# PSPS_AVNC_MITCH_2021-02-25.net
KiCad netlist of a schematic drawn in EAGLE
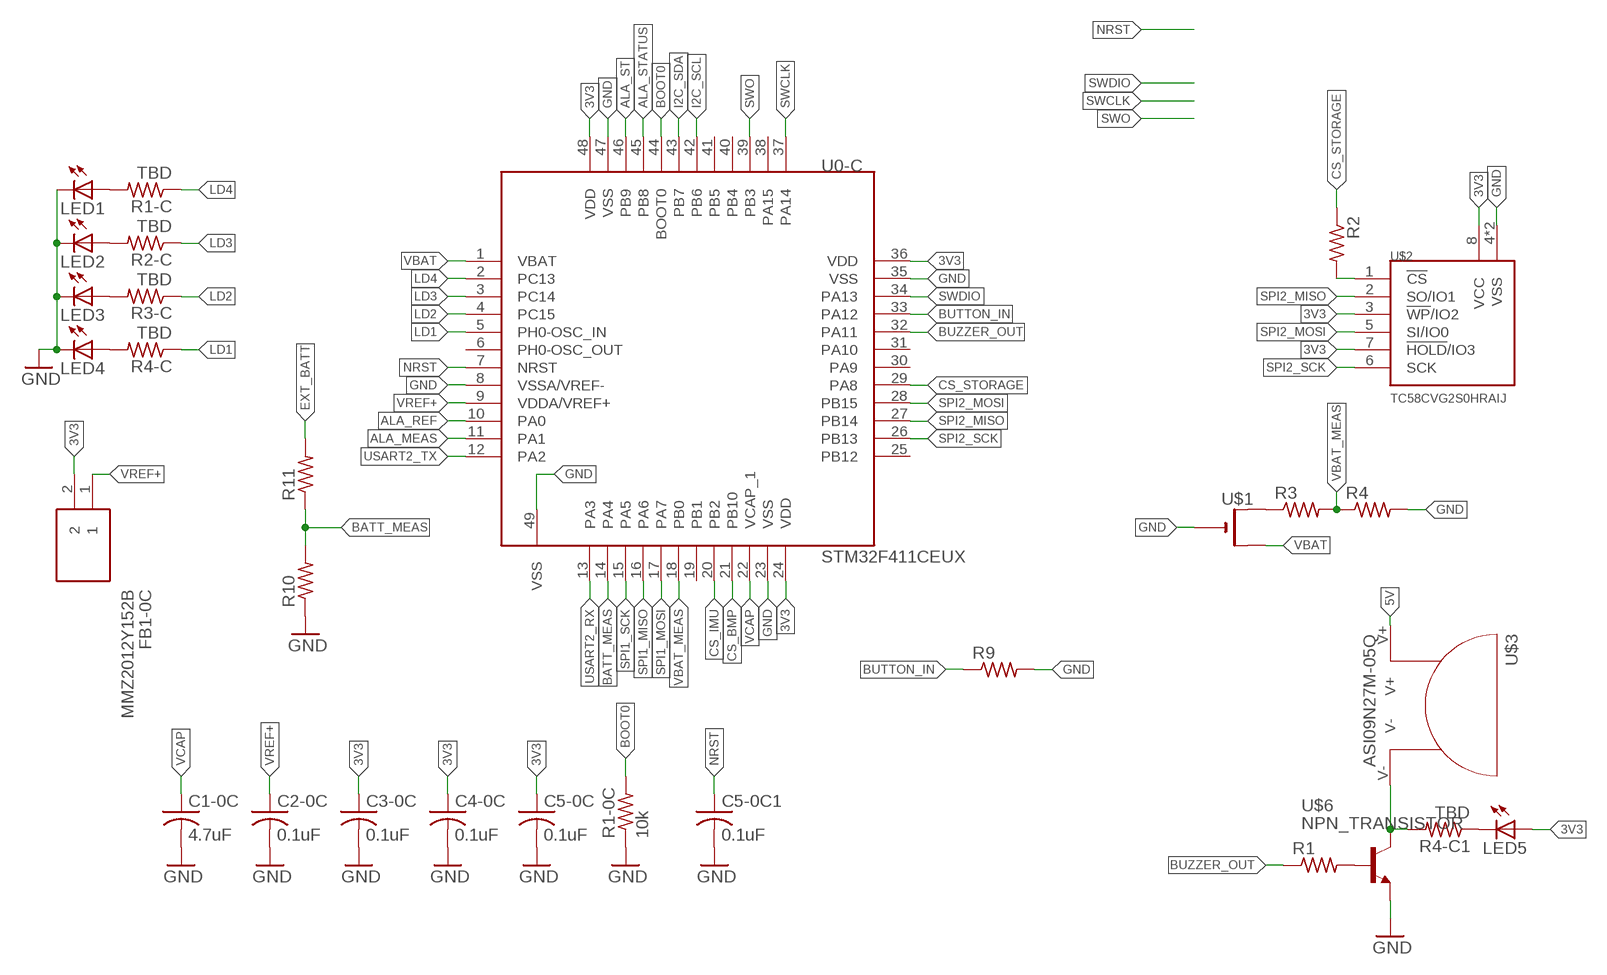
[diagram p0: schematic, sheet 1]
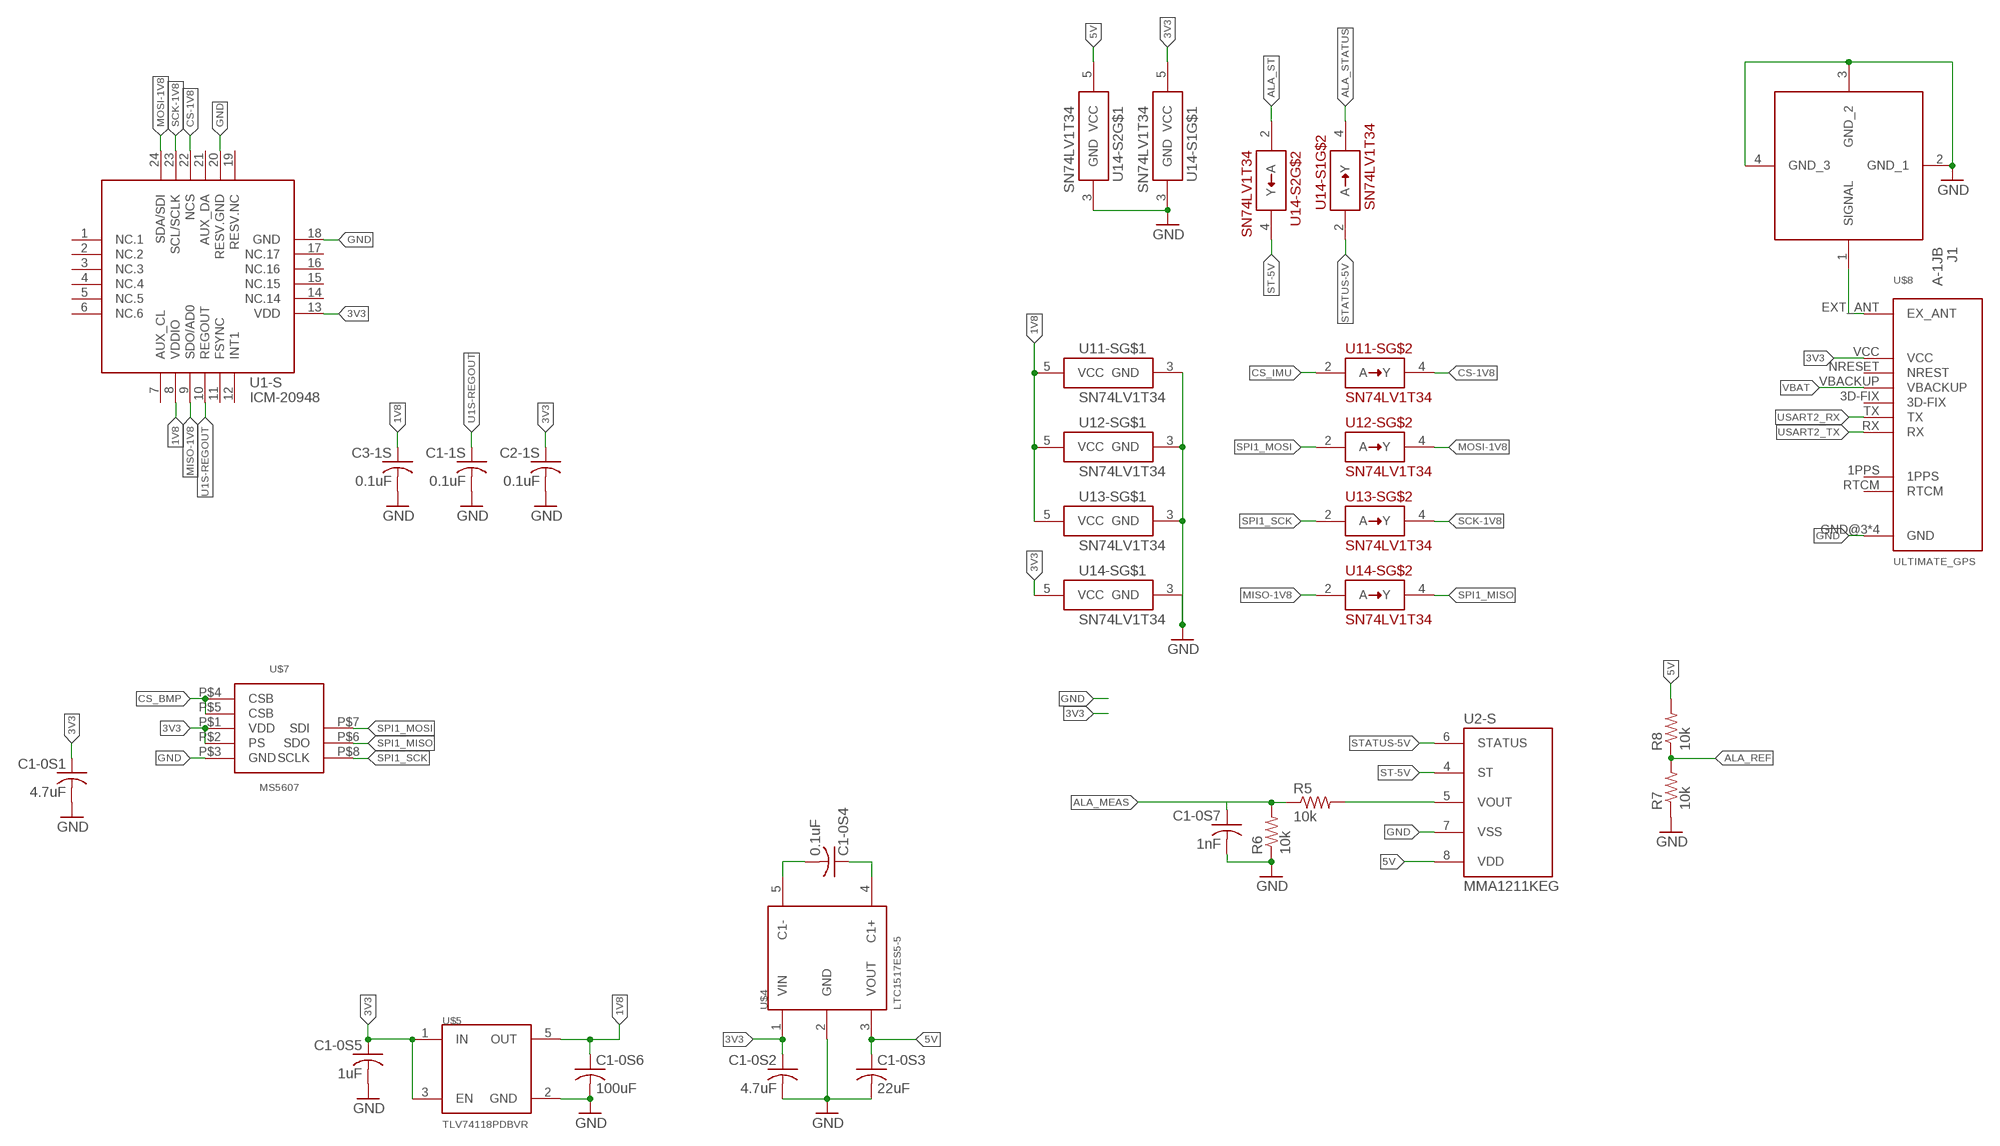
[diagram p1: schematic, sheet 2]

(export (version "E")
  (design (tool "Eeschema 10.0.6"))
  (components
    (comp (ref "C1-0S1")
      (value "4.7uF")
      (footprint "eagle-import:C0805")
      (libsource (lib "eagle-import") (part "C-USC0805"))
    )
    (comp (ref "C1-0S2")
      (value "4.7uF")
      (footprint "eagle-import:C0805")
      (libsource (lib "eagle-import") (part "C-USC0805"))
    )
    (comp (ref "C1-0S3")
      (value "22uF")
      (footprint "eagle-import:C0805")
      (libsource (lib "eagle-import") (part "C-USC0805"))
    )
    (comp (ref "C1-0S4")
      (value "0.1uF")
      (footprint "eagle-import:C0805")
      (libsource (lib "eagle-import") (part "C-USC0805"))
    )
    (comp (ref "C1-0S5")
      (value "1uF")
      (footprint "eagle-import:C0805")
      (libsource (lib "eagle-import") (part "C-USC0805"))
    )
    (comp (ref "C1-0S6")
      (value "100uF")
      (footprint "eagle-import:C0805")
      (libsource (lib "eagle-import") (part "C-USC0805"))
    )
    (comp (ref "C1-0S7")
      (value "1nF")
      (footprint "eagle-import:C0805")
      (libsource (lib "eagle-import") (part "C-USC0805"))
    )
    (comp (ref "C1-1S")
      (value "0.1uF")
      (footprint "eagle-import:C0805")
      (libsource (lib "eagle-import") (part "C-USC0805"))
    )
    (comp (ref "C2-1S")
      (value "0.1uF")
      (footprint "eagle-import:C0805")
      (libsource (lib "eagle-import") (part "C-USC0805"))
    )
    (comp (ref "C3-1S")
      (value "0.1uF")
      (footprint "eagle-import:C0805")
      (libsource (lib "eagle-import") (part "C-USC0805"))
    )
    (comp (ref "J1")
      (value "A-1JB")
      (footprint "eagle-import:A1JB")
      (fields (field (name "MOUSER_PART_NUMBER") "523-A-1JB"))
      (libsource (lib "eagle-import") (part "A-1JB"))
    )
    (comp (ref "R5")
      (value "10k")
      (footprint "eagle-import:R0805")
      (libsource (lib "eagle-import") (part "R-US_R0805"))
    )
    (comp (ref "R6")
      (value "10k")
      (footprint "eagle-import:R0805")
      (libsource (lib "eagle-import") (part "R-US_R0805"))
    )
    (comp (ref "R7")
      (value "10k")
      (footprint "eagle-import:R0805")
      (libsource (lib "eagle-import") (part "R-US_R0805"))
    )
    (comp (ref "R8")
      (value "10k")
      (footprint "eagle-import:R0805")
      (libsource (lib "eagle-import") (part "R-US_R0805"))
    )
    (comp (ref "U$4")
      (value "LTC1517ES5-5")
      (footprint "eagle-import:SOT95P280X145-5N")
      (libsource (lib "eagle-import") (part "LTC1517ES5-5"))
    )
    (comp (ref "U$5")
      (value "TLV74118PDBVR")
      (footprint "eagle-import:SOT95P280X145-5N")
      (libsource (lib "eagle-import") (part "TLV74118PDBVR"))
    )
    (comp (ref "U$7")
      (value "MS5607")
      (footprint "eagle-import:MS5607")
      (libsource (lib "eagle-import") (part "MS5607"))
    )
    (comp (ref "U$8")
      (value "ULTIMATE_GPS")
      (footprint "eagle-import:FGPMMOPA6H")
      (libsource (lib "eagle-import") (part "ULTIMATE_GPS"))
    )
    (comp (ref "U1-S")
      (value "ICM-20948")
      (footprint "eagle-import:QFN40P300X300X105-25T159X175")
      (libsource (lib "eagle-import") (part "ICM-20948"))
    )
    (comp (ref "U2-S")
      (value "MMA1211KEG")
      (footprint "eagle-import:SOIC127P1041X355-16N")
      (libsource (lib "eagle-import") (part "MMA1211KEG"))
    )
    (comp (ref "U11-S")
      (value "SN74LV1T34")
      (footprint "eagle-import:SOT65P210X110-5")
      (libsource (lib "eagle-import") (part "SN74LV1T34"))
    )
    (comp (ref "U12-S")
      (value "SN74LV1T34")
      (footprint "eagle-import:SOT65P210X110-5")
      (libsource (lib "eagle-import") (part "SN74LV1T34"))
    )
    (comp (ref "U13-S")
      (value "SN74LV1T34")
      (footprint "eagle-import:SOT65P210X110-5")
      (libsource (lib "eagle-import") (part "SN74LV1T34"))
    )
    (comp (ref "U14-S")
      (value "SN74LV1T34")
      (footprint "eagle-import:SOT65P210X110-5")
      (libsource (lib "eagle-import") (part "SN74LV1T34"))
    )
    (comp (ref "U14-S1")
      (value "SN74LV1T34")
      (footprint "eagle-import:SOT65P210X110-5")
      (libsource (lib "eagle-import") (part "SN74LV1T34"))
    )
    (comp (ref "U14-S2")
      (value "SN74LV1T34")
      (footprint "eagle-import:SOT65P210X110-5")
      (libsource (lib "eagle-import") (part "SN74LV1T34"))
    )
    (comp (ref "C1-0C")
      (value "4.7uF")
      (footprint "eagle-import:C0805")
      (libsource (lib "eagle-import") (part "C-USC0805"))
    )
    (comp (ref "C2-0C")
      (value "0.1uF")
      (footprint "eagle-import:C0805")
      (libsource (lib "eagle-import") (part "C-USC0805"))
    )
    (comp (ref "C3-0C")
      (value "0.1uF")
      (footprint "eagle-import:C0805")
      (libsource (lib "eagle-import") (part "C-USC0805"))
    )
    (comp (ref "C4-0C")
      (value "0.1uF")
      (footprint "eagle-import:C0805")
      (libsource (lib "eagle-import") (part "C-USC0805"))
    )
    (comp (ref "C5-0C")
      (value "0.1uF")
      (footprint "eagle-import:C0805")
      (libsource (lib "eagle-import") (part "C-USC0805"))
    )
    (comp (ref "C5-0C1")
      (value "0.1uF")
      (footprint "eagle-import:C0805")
      (libsource (lib "eagle-import") (part "C-USC0805"))
    )
    (comp (ref "FB1-0C")
      (value "MMZ2012Y152B")
      (footprint "eagle-import:BEADC2012X105N")
      (fields (field (name "MOUSER_PART_NUMBER") "810-MMZ2012Y152B"))
      (libsource (lib "eagle-import") (part "MMZ2012Y152B"))
    )
    (comp (ref "LED1")
      (value "LEDCHIPLED_0805")
      (footprint "eagle-import:CHIPLED_0805")
      (libsource (lib "eagle-import") (part "LEDCHIPLED_0805"))
    )
    (comp (ref "LED2")
      (value "LEDCHIPLED_0805")
      (footprint "eagle-import:CHIPLED_0805")
      (libsource (lib "eagle-import") (part "LEDCHIPLED_0805"))
    )
    (comp (ref "LED3")
      (value "LEDCHIPLED_0805")
      (footprint "eagle-import:CHIPLED_0805")
      (libsource (lib "eagle-import") (part "LEDCHIPLED_0805"))
    )
    (comp (ref "LED4")
      (value "LEDCHIPLED_0805")
      (footprint "eagle-import:CHIPLED_0805")
      (libsource (lib "eagle-import") (part "LEDCHIPLED_0805"))
    )
    (comp (ref "LED5")
      (value "LEDCHIPLED_0805")
      (footprint "eagle-import:CHIPLED_0805")
      (libsource (lib "eagle-import") (part "LEDCHIPLED_0805"))
    )
    (comp (ref "R1")
      (value "R-US_R0805")
      (footprint "eagle-import:R0805")
      (libsource (lib "eagle-import") (part "R-US_R0805"))
    )
    (comp (ref "R1-0C")
      (value "10k")
      (footprint "eagle-import:R0805")
      (libsource (lib "eagle-import") (part "R-US_R0805"))
    )
    (comp (ref "R1-C")
      (value "TBD")
      (footprint "eagle-import:R0805")
      (libsource (lib "eagle-import") (part "R-US_R0805"))
    )
    (comp (ref "R2")
      (value "R-US_R0805")
      (footprint "eagle-import:R0805")
      (libsource (lib "eagle-import") (part "R-US_R0805"))
    )
    (comp (ref "R2-C")
      (value "TBD")
      (footprint "eagle-import:R0805")
      (libsource (lib "eagle-import") (part "R-US_R0805"))
    )
    (comp (ref "R3")
      (value "R-US_R0805")
      (footprint "eagle-import:R0805")
      (libsource (lib "eagle-import") (part "R-US_R0805"))
    )
    (comp (ref "R3-C")
      (value "TBD")
      (footprint "eagle-import:R0805")
      (libsource (lib "eagle-import") (part "R-US_R0805"))
    )
    (comp (ref "R4")
      (value "R-US_R0805")
      (footprint "eagle-import:R0805")
      (libsource (lib "eagle-import") (part "R-US_R0805"))
    )
    (comp (ref "R4-C")
      (value "TBD")
      (footprint "eagle-import:R0805")
      (libsource (lib "eagle-import") (part "R-US_R0805"))
    )
    (comp (ref "R4-C1")
      (value "TBD")
      (footprint "eagle-import:R0805")
      (libsource (lib "eagle-import") (part "R-US_R0805"))
    )
    (comp (ref "R9")
      (value "R-US_R0805")
      (footprint "eagle-import:R0805")
      (libsource (lib "eagle-import") (part "R-US_R0805"))
    )
    (comp (ref "R10")
      (value "R-US_R0805")
      (footprint "eagle-import:R0805")
      (libsource (lib "eagle-import") (part "R-US_R0805"))
    )
    (comp (ref "R11")
      (value "R-US_R0805")
      (footprint "eagle-import:R0805")
      (libsource (lib "eagle-import") (part "R-US_R0805"))
    )
    (comp (ref "U$1")
      (value "CR1220SMT")
      (footprint "eagle-import:CR1220-SMD")
      (libsource (lib "eagle-import") (part "CR1220SMT"))
    )
    (comp (ref "U$2")
      (value "TC58CVG2S0HRAIJ")
      (footprint "eagle-import:SON127P800X600X80-9T350X440N")
      (libsource (lib "eagle-import") (part "TC58CVG2S0HRAIJ"))
    )
    (comp (ref "U$3")
      (value "ASI09N27M-05Q")
      (footprint "eagle-import:ASI09N27M-05Q")
      (libsource (lib "eagle-import") (part "ASI09N27M-05Q"))
    )
    (comp (ref "U$6")
      (value "NPN_TRANSISTOR")
      (footprint "eagle-import:SOT23")
      (libsource (lib "eagle-import") (part "NPN_TRANSISTOR"))
    )
    (comp (ref "U0-C")
      (value "STM32F411CEUX")
      (footprint "eagle-import:QFN50P700X700X50-49T560N")
      (libsource (lib "eagle-import") (part "STM32F411CEUX"))
    )
  )
  (nets
    (net (code "1") (name "1V8") (class "Default")
      (node (ref "C1-0S6") (pin "1") (pinfunction "1_1") (pintype "passive"))
      (node (ref "C3-1S") (pin "1") (pinfunction "1_1") (pintype "passive"))
      (node (ref "U$5") (pin "5") (pinfunction "OUT_5") (pintype "bidirectional"))
      (node (ref "U1-S") (pin "8") (pinfunction "VDDIO_8") (pintype "bidirectional"))
      (node (ref "U11-S") (pin "5") (pinfunction "VCC_5") (pintype "bidirectional"))
      (node (ref "U12-S") (pin "5") (pinfunction "VCC_5") (pintype "bidirectional"))
      (node (ref "U13-S") (pin "5") (pinfunction "VCC_5") (pintype "bidirectional"))
    )
    (net (code "2") (name "3V3") (class "Default")
      (node (ref "C1-0S1") (pin "1") (pinfunction "1_1") (pintype "passive"))
      (node (ref "C1-0S2") (pin "1") (pinfunction "1_1") (pintype "passive"))
      (node (ref "C1-0S5") (pin "1") (pinfunction "1_1") (pintype "passive"))
      (node (ref "C2-1S") (pin "1") (pinfunction "1_1") (pintype "passive"))
      (node (ref "C3-0C") (pin "1") (pinfunction "1_1") (pintype "passive"))
      (node (ref "C4-0C") (pin "1") (pinfunction "1_1") (pintype "passive"))
      (node (ref "C5-0C") (pin "1") (pinfunction "1_1") (pintype "passive"))
      (node (ref "FB1-0C") (pin "2") (pinfunction "2_2") (pintype "bidirectional"))
      (node (ref "LED5") (pin "A") (pinfunction "A_A") (pintype "passive"))
      (node (ref "U$2") (pin "3") (pinfunction "~{WP}/IO2_3") (pintype "bidirectional"))
      (node (ref "U$2") (pin "7") (pinfunction "~{HOLD}/IO3_7") (pintype "bidirectional"))
      (node (ref "U$2") (pin "8") (pinfunction "VCC_8") (pintype "bidirectional"))
      (node (ref "U$4") (pin "1") (pinfunction "VIN_1") (pintype "bidirectional"))
      (node (ref "U$5") (pin "1") (pinfunction "IN_1") (pintype "bidirectional"))
      (node (ref "U$5") (pin "3") (pinfunction "EN_3") (pintype "bidirectional"))
      (node (ref "U$7") (pin "P$1") (pinfunction "VDD_P$1") (pintype "bidirectional"))
      (node (ref "U$7") (pin "P$2") (pinfunction "PS_P$2") (pintype "bidirectional"))
      (node (ref "U$8") (pin "VCC") (pinfunction "VCC_VCC") (pintype "bidirectional"))
      (node (ref "U0-C") (pin "24") (pinfunction "VDD_24") (pintype "bidirectional"))
      (node (ref "U0-C") (pin "36") (pinfunction "VDD_36") (pintype "bidirectional"))
      (node (ref "U0-C") (pin "48") (pinfunction "VDD_48") (pintype "bidirectional"))
      (node (ref "U1-S") (pin "13") (pinfunction "VDD_13") (pintype "bidirectional"))
      (node (ref "U14-S") (pin "5") (pinfunction "VCC_5") (pintype "bidirectional"))
      (node (ref "U14-S1") (pin "5") (pinfunction "VCC_5") (pintype "bidirectional"))
    )
    (net (code "3") (name "5V") (class "Default")
      (node (ref "C1-0S3") (pin "1") (pinfunction "1_1") (pintype "passive"))
      (node (ref "R8") (pin "2") (pinfunction "2_2") (pintype "passive"))
      (node (ref "U$3") (pin "V+") (pinfunction "V+_V+") (pintype "bidirectional"))
      (node (ref "U$4") (pin "3") (pinfunction "VOUT_3") (pintype "bidirectional"))
      (node (ref "U14-S2") (pin "5") (pinfunction "VCC_5") (pintype "bidirectional"))
      (node (ref "U2-S") (pin "8") (pinfunction "VDD_8") (pintype "bidirectional"))
    )
    (net (code "4") (name "ALA_MEAS") (class "Default")
      (node (ref "C1-0S7") (pin "1") (pinfunction "1_1") (pintype "passive"))
      (node (ref "R5") (pin "1") (pinfunction "1_1") (pintype "passive"))
      (node (ref "R6") (pin "2") (pinfunction "2_2") (pintype "passive"))
      (node (ref "U0-C") (pin "11") (pinfunction "PA1_11") (pintype "bidirectional"))
    )
    (net (code "5") (name "ALA_REF") (class "Default")
      (node (ref "R7") (pin "2") (pinfunction "2_2") (pintype "passive"))
      (node (ref "R8") (pin "1") (pinfunction "1_1") (pintype "passive"))
      (node (ref "U0-C") (pin "10") (pinfunction "PA0_10") (pintype "bidirectional"))
    )
    (net (code "6") (name "ALA_ST") (class "Default")
      (node (ref "U0-C") (pin "46") (pinfunction "PB9_46") (pintype "bidirectional"))
      (node (ref "U14-S2") (pin "2") (pinfunction "A_2") (pintype "bidirectional"))
    )
    (net (code "7") (name "ALA_STATUS") (class "Default")
      (node (ref "U0-C") (pin "45") (pinfunction "PB8_45") (pintype "bidirectional"))
      (node (ref "U14-S1") (pin "4") (pinfunction "Y_4") (pintype "bidirectional"))
    )
    (net (code "8") (name "BATT_MEAS") (class "Default")
      (node (ref "R10") (pin "2") (pinfunction "2_2") (pintype "passive"))
      (node (ref "R11") (pin "1") (pinfunction "1_1") (pintype "passive"))
      (node (ref "U0-C") (pin "14") (pinfunction "PA4_14") (pintype "bidirectional"))
    )
    (net (code "9") (name "BOOT0") (class "Default")
      (node (ref "R1-0C") (pin "2") (pinfunction "2_2") (pintype "passive"))
      (node (ref "U0-C") (pin "44") (pinfunction "BOOT0_44") (pintype "bidirectional"))
    )
    (net (code "10") (name "BUTTON_IN") (class "Default")
      (node (ref "R9") (pin "1") (pinfunction "1_1") (pintype "passive"))
      (node (ref "U0-C") (pin "33") (pinfunction "PA12_33") (pintype "bidirectional"))
    )
    (net (code "11") (name "BUZZER_OUT") (class "Default")
      (node (ref "R1") (pin "1") (pinfunction "1_1") (pintype "passive"))
      (node (ref "U0-C") (pin "32") (pinfunction "PA11_32") (pintype "bidirectional"))
    )
    (net (code "12") (name "CS-1V8") (class "Default")
      (node (ref "U1-S") (pin "22") (pinfunction "NCS_22") (pintype "bidirectional"))
      (node (ref "U11-S") (pin "4") (pinfunction "Y_4") (pintype "bidirectional"))
    )
    (net (code "13") (name "CS_BMP") (class "Default")
      (node (ref "U$7") (pin "P$4") (pinfunction "CSB_P$4") (pintype "bidirectional"))
      (node (ref "U$7") (pin "P$5") (pinfunction "CSB_P$5") (pintype "bidirectional"))
      (node (ref "U0-C") (pin "21") (pinfunction "PB10_21") (pintype "bidirectional"))
    )
    (net (code "14") (name "CS_IMU") (class "Default")
      (node (ref "U0-C") (pin "20") (pinfunction "PB2_20") (pintype "bidirectional"))
      (node (ref "U11-S") (pin "2") (pinfunction "A_2") (pintype "bidirectional"))
    )
    (net (code "15") (name "CS_STORAGE") (class "Default")
      (node (ref "R2") (pin "1") (pinfunction "1_1") (pintype "passive"))
      (node (ref "U0-C") (pin "29") (pinfunction "PA8_29") (pintype "bidirectional"))
    )
    (net (code "16") (name "EXT_BATT") (class "Default")
      (node (ref "R11") (pin "2") (pinfunction "2_2") (pintype "passive"))
    )
    (net (code "17") (name "GND") (class "Default")
      (node (ref "C1-0C") (pin "2") (pinfunction "2_2") (pintype "passive"))
      (node (ref "C1-0S1") (pin "2") (pinfunction "2_2") (pintype "passive"))
      (node (ref "C1-0S2") (pin "2") (pinfunction "2_2") (pintype "passive"))
      (node (ref "C1-0S3") (pin "2") (pinfunction "2_2") (pintype "passive"))
      (node (ref "C1-0S5") (pin "2") (pinfunction "2_2") (pintype "passive"))
      (node (ref "C1-0S6") (pin "2") (pinfunction "2_2") (pintype "passive"))
      (node (ref "C1-0S7") (pin "2") (pinfunction "2_2") (pintype "passive"))
      (node (ref "C1-1S") (pin "2") (pinfunction "2_2") (pintype "passive"))
      (node (ref "C2-0C") (pin "2") (pinfunction "2_2") (pintype "passive"))
      (node (ref "C2-1S") (pin "2") (pinfunction "2_2") (pintype "passive"))
      (node (ref "C3-0C") (pin "2") (pinfunction "2_2") (pintype "passive"))
      (node (ref "C3-1S") (pin "2") (pinfunction "2_2") (pintype "passive"))
      (node (ref "C4-0C") (pin "2") (pinfunction "2_2") (pintype "passive"))
      (node (ref "C5-0C") (pin "2") (pinfunction "2_2") (pintype "passive"))
      (node (ref "C5-0C1") (pin "2") (pinfunction "2_2") (pintype "passive"))
      (node (ref "J1") (pin "2") (pinfunction "GND_1_2") (pintype "bidirectional"))
      (node (ref "J1") (pin "3") (pinfunction "GND_2_3") (pintype "bidirectional"))
      (node (ref "J1") (pin "4") (pinfunction "GND_3_4") (pintype "bidirectional"))
      (node (ref "LED1") (pin "C") (pinfunction "C_C") (pintype "passive"))
      (node (ref "LED2") (pin "C") (pinfunction "C_C") (pintype "passive"))
      (node (ref "LED3") (pin "C") (pinfunction "C_C") (pintype "passive"))
      (node (ref "LED4") (pin "C") (pinfunction "C_C") (pintype "passive"))
      (node (ref "R1-0C") (pin "1") (pinfunction "1_1") (pintype "passive"))
      (node (ref "R10") (pin "1") (pinfunction "1_1") (pintype "passive"))
      (node (ref "R4") (pin "2") (pinfunction "2_2") (pintype "passive"))
      (node (ref "R6") (pin "1") (pinfunction "1_1") (pintype "passive"))
      (node (ref "R7") (pin "1") (pinfunction "1_1") (pintype "passive"))
      (node (ref "R9") (pin "2") (pinfunction "2_2") (pintype "passive"))
      (node (ref "U$1") (pin "-") (pinfunction "-_-") (pintype "passive"))
      (node (ref "U$2") (pin "4") (pinfunction "VSS_4") (pintype "bidirectional"))
      (node (ref "U$2") (pin "9") (pinfunction "VSS_9") (pintype "bidirectional"))
      (node (ref "U$4") (pin "2") (pinfunction "GND_2") (pintype "bidirectional"))
      (node (ref "U$5") (pin "2") (pinfunction "GND_2") (pintype "bidirectional"))
      (node (ref "U$6") (pin "3") (pinfunction "E_3") (pintype "passive"))
      (node (ref "U$7") (pin "P$3") (pinfunction "GND_P$3") (pintype "bidirectional"))
      (node (ref "U$8") (pin "GND@12") (pinfunction "GND_GND@12") (pintype "bidirectional"))
      (node (ref "U$8") (pin "GND@19") (pinfunction "GND_GND@19") (pintype "bidirectional"))
      (node (ref "U$8") (pin "GND@3") (pinfunction "GND_GND@3") (pintype "bidirectional"))
      (node (ref "U$8") (pin "GND@8") (pinfunction "GND_GND@8") (pintype "bidirectional"))
      (node (ref "U0-C") (pin "23") (pinfunction "VSS_23") (pintype "bidirectional"))
      (node (ref "U0-C") (pin "35") (pinfunction "VSS_35") (pintype "bidirectional"))
      (node (ref "U0-C") (pin "47") (pinfunction "VSS_47") (pintype "bidirectional"))
      (node (ref "U0-C") (pin "49") (pinfunction "VSS_49") (pintype "bidirectional"))
      (node (ref "U0-C") (pin "8") (pinfunction "VSSA/VREF-_8") (pintype "bidirectional"))
      (node (ref "U1-S") (pin "18") (pinfunction "GND_18") (pintype "bidirectional"))
      (node (ref "U1-S") (pin "20") (pinfunction "RESV.GND_20") (pintype "bidirectional"))
      (node (ref "U11-S") (pin "3") (pinfunction "GND_3") (pintype "bidirectional"))
      (node (ref "U12-S") (pin "3") (pinfunction "GND_3") (pintype "bidirectional"))
      (node (ref "U13-S") (pin "3") (pinfunction "GND_3") (pintype "bidirectional"))
      (node (ref "U14-S") (pin "3") (pinfunction "GND_3") (pintype "bidirectional"))
      (node (ref "U14-S1") (pin "3") (pinfunction "GND_3") (pintype "bidirectional"))
      (node (ref "U14-S2") (pin "3") (pinfunction "GND_3") (pintype "bidirectional"))
      (node (ref "U2-S") (pin "7") (pinfunction "VSS_7") (pintype "bidirectional"))
    )
    (net (code "18") (name "I2C_SCL") (class "Default")
      (node (ref "U0-C") (pin "42") (pinfunction "PB6_42") (pintype "bidirectional"))
    )
    (net (code "19") (name "I2C_SDA") (class "Default")
      (node (ref "U0-C") (pin "43") (pinfunction "PB7_43") (pintype "bidirectional"))
    )
    (net (code "20") (name "LD1") (class "Default")
      (node (ref "R4-C") (pin "1") (pinfunction "1_1") (pintype "passive"))
      (node (ref "U0-C") (pin "5") (pinfunction "PH0-OSC_IN_5") (pintype "bidirectional"))
    )
    (net (code "21") (name "LD2") (class "Default")
      (node (ref "R3-C") (pin "1") (pinfunction "1_1") (pintype "passive"))
      (node (ref "U0-C") (pin "4") (pinfunction "PC15_4") (pintype "bidirectional"))
    )
    (net (code "22") (name "LD3") (class "Default")
      (node (ref "R2-C") (pin "1") (pinfunction "1_1") (pintype "passive"))
      (node (ref "U0-C") (pin "3") (pinfunction "PC14_3") (pintype "bidirectional"))
    )
    (net (code "23") (name "LD4") (class "Default")
      (node (ref "R1-C") (pin "1") (pinfunction "1_1") (pintype "passive"))
      (node (ref "U0-C") (pin "2") (pinfunction "PC13_2") (pintype "bidirectional"))
    )
    (net (code "24") (name "MISO-1V8") (class "Default")
      (node (ref "U1-S") (pin "9") (pinfunction "SDO/AD0_9") (pintype "bidirectional"))
      (node (ref "U14-S") (pin "2") (pinfunction "A_2") (pintype "bidirectional"))
    )
    (net (code "25") (name "MOSI-1V8") (class "Default")
      (node (ref "U1-S") (pin "24") (pinfunction "SDA/SDI_24") (pintype "bidirectional"))
      (node (ref "U12-S") (pin "4") (pinfunction "Y_4") (pintype "bidirectional"))
    )
    (net (code "26") (name "NRST") (class "Default")
      (node (ref "C5-0C1") (pin "1") (pinfunction "1_1") (pintype "passive"))
      (node (ref "U0-C") (pin "7") (pinfunction "NRST_7") (pintype "bidirectional"))
    )
    (net (code "27") (name "Net-(J1-SIGNAL)") (class "Default")
      (node (ref "J1") (pin "1") (pinfunction "SIGNAL_1") (pintype "bidirectional"))
      (node (ref "U$8") (pin "EXT_ANT") (pinfunction "EX_ANT_EXT_ANT") (pintype "bidirectional"))
    )
    (net (code "28") (name "Net-(LED1-PadA)") (class "Default")
      (node (ref "LED1") (pin "A") (pinfunction "A_A") (pintype "passive"))
      (node (ref "R1-C") (pin "2") (pinfunction "2_2") (pintype "passive"))
    )
    (net (code "29") (name "Net-(LED2-PadA)") (class "Default")
      (node (ref "LED2") (pin "A") (pinfunction "A_A") (pintype "passive"))
      (node (ref "R2-C") (pin "2") (pinfunction "2_2") (pintype "passive"))
    )
    (net (code "30") (name "Net-(LED3-PadA)") (class "Default")
      (node (ref "LED3") (pin "A") (pinfunction "A_A") (pintype "passive"))
      (node (ref "R3-C") (pin "2") (pinfunction "2_2") (pintype "passive"))
    )
    (net (code "31") (name "Net-(LED4-PadA)") (class "Default")
      (node (ref "LED4") (pin "A") (pinfunction "A_A") (pintype "passive"))
      (node (ref "R4-C") (pin "2") (pinfunction "2_2") (pintype "passive"))
    )
    (net (code "32") (name "Net-(LED5-PadC)") (class "Default")
      (node (ref "LED5") (pin "C") (pinfunction "C_C") (pintype "passive"))
      (node (ref "R4-C1") (pin "1") (pinfunction "1_1") (pintype "passive"))
    )
    (net (code "33") (name "Net-(U$1-+)") (class "Default")
      (node (ref "R3") (pin "1") (pinfunction "1_1") (pintype "passive"))
      (node (ref "U$1") (pin "+$1") (pinfunction "+_+$1") (pintype "passive"))
    )
    (net (code "34") (name "Net-(U$2-~{CS})") (class "Default")
      (node (ref "R2") (pin "2") (pinfunction "2_2") (pintype "passive"))
      (node (ref "U$2") (pin "1") (pinfunction "~{CS}_1") (pintype "bidirectional"))
    )
    (net (code "35") (name "Net-(U$4-C1+)") (class "Default")
      (node (ref "C1-0S4") (pin "1") (pinfunction "1_1") (pintype "passive"))
      (node (ref "U$4") (pin "4") (pinfunction "C1+_4") (pintype "bidirectional"))
    )
    (net (code "36") (name "Net-(U$4-C1-)") (class "Default")
      (node (ref "C1-0S4") (pin "2") (pinfunction "2_2") (pintype "passive"))
      (node (ref "U$4") (pin "5") (pinfunction "C1-_5") (pintype "bidirectional"))
    )
    (net (code "37") (name "Net-(U$6-B)") (class "Default")
      (node (ref "R1") (pin "2") (pinfunction "2_2") (pintype "passive"))
      (node (ref "U$6") (pin "1") (pinfunction "B_1") (pintype "passive"))
    )
    (net (code "38") (name "Net-(U$6-C)") (class "Default")
      (node (ref "R4-C1") (pin "2") (pinfunction "2_2") (pintype "passive"))
      (node (ref "U$3") (pin "V-") (pinfunction "V-_V-") (pintype "bidirectional"))
      (node (ref "U$6") (pin "2") (pinfunction "C_2") (pintype "passive"))
    )
    (net (code "39") (name "Net-(U2-S-VOUT)") (class "Default")
      (node (ref "R5") (pin "2") (pinfunction "2_2") (pintype "passive"))
      (node (ref "U2-S") (pin "5") (pinfunction "VOUT_5") (pintype "bidirectional"))
    )
    (net (code "40") (name "SCK-1V8") (class "Default")
      (node (ref "U1-S") (pin "23") (pinfunction "SCL/SCLK_23") (pintype "bidirectional"))
      (node (ref "U13-S") (pin "4") (pinfunction "Y_4") (pintype "bidirectional"))
    )
    (net (code "41") (name "SPI1_MISO") (class "Default")
      (node (ref "U$7") (pin "P$6") (pinfunction "SDO_P$6") (pintype "bidirectional"))
      (node (ref "U0-C") (pin "16") (pinfunction "PA6_16") (pintype "bidirectional"))
      (node (ref "U14-S") (pin "4") (pinfunction "Y_4") (pintype "bidirectional"))
    )
    (net (code "42") (name "SPI1_MOSI") (class "Default")
      (node (ref "U$7") (pin "P$7") (pinfunction "SDI_P$7") (pintype "bidirectional"))
      (node (ref "U0-C") (pin "17") (pinfunction "PA7_17") (pintype "bidirectional"))
      (node (ref "U12-S") (pin "2") (pinfunction "A_2") (pintype "bidirectional"))
    )
    (net (code "43") (name "SPI1_SCK") (class "Default")
      (node (ref "U$7") (pin "P$8") (pinfunction "SCLK_P$8") (pintype "bidirectional"))
      (node (ref "U0-C") (pin "15") (pinfunction "PA5_15") (pintype "bidirectional"))
      (node (ref "U13-S") (pin "2") (pinfunction "A_2") (pintype "bidirectional"))
    )
    (net (code "44") (name "SPI2_MISO") (class "Default")
      (node (ref "U$2") (pin "2") (pinfunction "SO/IO1_2") (pintype "bidirectional"))
      (node (ref "U0-C") (pin "27") (pinfunction "PB14_27") (pintype "bidirectional"))
    )
    (net (code "45") (name "SPI2_MOSI") (class "Default")
      (node (ref "U$2") (pin "5") (pinfunction "SI/IO0_5") (pintype "bidirectional"))
      (node (ref "U0-C") (pin "28") (pinfunction "PB15_28") (pintype "bidirectional"))
    )
    (net (code "46") (name "SPI2_SCK") (class "Default")
      (node (ref "U$2") (pin "6") (pinfunction "SCK_6") (pintype "bidirectional"))
      (node (ref "U0-C") (pin "26") (pinfunction "PB13_26") (pintype "bidirectional"))
    )
    (net (code "47") (name "ST-5V") (class "Default")
      (node (ref "U14-S2") (pin "4") (pinfunction "Y_4") (pintype "bidirectional"))
      (node (ref "U2-S") (pin "4") (pinfunction "ST_4") (pintype "bidirectional"))
    )
    (net (code "48") (name "STATUS-5V") (class "Default")
      (node (ref "U14-S1") (pin "2") (pinfunction "A_2") (pintype "bidirectional"))
      (node (ref "U2-S") (pin "6") (pinfunction "STATUS_6") (pintype "bidirectional"))
    )
    (net (code "49") (name "SWCLK") (class "Default")
      (node (ref "U0-C") (pin "37") (pinfunction "PA14_37") (pintype "bidirectional"))
    )
    (net (code "50") (name "SWDIO") (class "Default")
      (node (ref "U0-C") (pin "34") (pinfunction "PA13_34") (pintype "bidirectional"))
    )
    (net (code "51") (name "SWO") (class "Default")
      (node (ref "U0-C") (pin "39") (pinfunction "PB3_39") (pintype "bidirectional"))
    )
    (net (code "52") (name "U1S-REGOUT") (class "Default")
      (node (ref "C1-1S") (pin "1") (pinfunction "1_1") (pintype "passive"))
      (node (ref "U1-S") (pin "10") (pinfunction "REGOUT_10") (pintype "bidirectional"))
    )
    (net (code "53") (name "USART2_RX") (class "Default")
      (node (ref "U$8") (pin "TX") (pinfunction "TX_TX") (pintype "bidirectional"))
      (node (ref "U0-C") (pin "13") (pinfunction "PA3_13") (pintype "bidirectional"))
    )
    (net (code "54") (name "USART2_TX") (class "Default")
      (node (ref "U$8") (pin "RX") (pinfunction "RX_RX") (pintype "bidirectional"))
      (node (ref "U0-C") (pin "12") (pinfunction "PA2_12") (pintype "bidirectional"))
    )
    (net (code "55") (name "VBAT") (class "Default")
      (node (ref "U$1") (pin "+$2") (pinfunction "+1_+$2") (pintype "passive"))
      (node (ref "U$8") (pin "VBACKUP") (pinfunction "VBACKUP_VBACKUP") (pintype "bidirectional"))
      (node (ref "U0-C") (pin "1") (pinfunction "VBAT_1") (pintype "bidirectional"))
    )
    (net (code "56") (name "VBAT_MEAS") (class "Default")
      (node (ref "R3") (pin "2") (pinfunction "2_2") (pintype "passive"))
      (node (ref "R4") (pin "1") (pinfunction "1_1") (pintype "passive"))
      (node (ref "U0-C") (pin "18") (pinfunction "PB0_18") (pintype "bidirectional"))
    )
    (net (code "57") (name "VCAP") (class "Default")
      (node (ref "C1-0C") (pin "1") (pinfunction "1_1") (pintype "passive"))
      (node (ref "U0-C") (pin "22") (pinfunction "VCAP_1_22") (pintype "bidirectional"))
    )
    (net (code "58") (name "VREF+") (class "Default")
      (node (ref "C2-0C") (pin "1") (pinfunction "1_1") (pintype "passive"))
      (node (ref "FB1-0C") (pin "1") (pinfunction "1_1") (pintype "bidirectional"))
      (node (ref "U0-C") (pin "9") (pinfunction "VDDA/VREF+_9") (pintype "bidirectional"))
    )
    (net (code "59") (name "unconnected-(U$8-NREST-PadNRESET)") (class "Default")
      (node (ref "U$8") (pin "NRESET") (pinfunction "NREST_NRESET") (pintype "bidirectional"))
    )
    (net (code "60") (name "unconnected-(U$8-Pad1PPS)") (class "Default")
      (node (ref "U$8") (pin "1PPS") (pinfunction "1PPS_1PPS") (pintype "bidirectional"))
    )
    (net (code "61") (name "unconnected-(U$8-Pad3D-FIX)") (class "Default")
      (node (ref "U$8") (pin "3D-FIX") (pinfunction "3D-FIX_3D-FIX") (pintype "bidirectional"))
    )
    (net (code "62") (name "unconnected-(U$8-PadRTCM)") (class "Default")
      (node (ref "U$8") (pin "RTCM") (pinfunction "RTCM_RTCM") (pintype "bidirectional"))
    )
    (net (code "63") (name "unconnected-(U0-C-PA9-Pad30)") (class "Default")
      (node (ref "U0-C") (pin "30") (pinfunction "PA9_30") (pintype "bidirectional"))
    )
    (net (code "64") (name "unconnected-(U0-C-PA10-Pad31)") (class "Default")
      (node (ref "U0-C") (pin "31") (pinfunction "PA10_31") (pintype "bidirectional"))
    )
    (net (code "65") (name "unconnected-(U0-C-PA15-Pad38)") (class "Default")
      (node (ref "U0-C") (pin "38") (pinfunction "PA15_38") (pintype "bidirectional"))
    )
    (net (code "66") (name "unconnected-(U0-C-PB1-Pad19)") (class "Default")
      (node (ref "U0-C") (pin "19") (pinfunction "PB1_19") (pintype "bidirectional"))
    )
    (net (code "67") (name "unconnected-(U0-C-PB4-Pad40)") (class "Default")
      (node (ref "U0-C") (pin "40") (pinfunction "PB4_40") (pintype "bidirectional"))
    )
    (net (code "68") (name "unconnected-(U0-C-PB5-Pad41)") (class "Default")
      (node (ref "U0-C") (pin "41") (pinfunction "PB5_41") (pintype "bidirectional"))
    )
    (net (code "69") (name "unconnected-(U0-C-PB12-Pad25)") (class "Default")
      (node (ref "U0-C") (pin "25") (pinfunction "PB12_25") (pintype "bidirectional"))
    )
    (net (code "70") (name "unconnected-(U0-C-PH0-OSC_OUT-Pad6)") (class "Default")
      (node (ref "U0-C") (pin "6") (pinfunction "PH0-OSC_OUT_6") (pintype "bidirectional"))
    )
    (net (code "71") (name "unconnected-(U1-S-AUX_CL-Pad7)") (class "Default")
      (node (ref "U1-S") (pin "7") (pinfunction "AUX_CL_7") (pintype "bidirectional"))
    )
    (net (code "72") (name "unconnected-(U1-S-AUX_DA-Pad21)") (class "Default")
      (node (ref "U1-S") (pin "21") (pinfunction "AUX_DA_21") (pintype "bidirectional"))
    )
    (net (code "73") (name "unconnected-(U1-S-FSYNC-Pad11)") (class "Default")
      (node (ref "U1-S") (pin "11") (pinfunction "FSYNC_11") (pintype "bidirectional"))
    )
    (net (code "74") (name "unconnected-(U1-S-INT1-Pad12)") (class "Default")
      (node (ref "U1-S") (pin "12") (pinfunction "INT1_12") (pintype "bidirectional"))
    )
    (net (code "75") (name "unconnected-(U1-S-NC.1-Pad1)") (class "Default")
      (node (ref "U1-S") (pin "1") (pinfunction "NC.1_1") (pintype "bidirectional"))
    )
    (net (code "76") (name "unconnected-(U1-S-NC.2-Pad2)") (class "Default")
      (node (ref "U1-S") (pin "2") (pinfunction "NC.2_2") (pintype "bidirectional"))
    )
    (net (code "77") (name "unconnected-(U1-S-NC.3-Pad3)") (class "Default")
      (node (ref "U1-S") (pin "3") (pinfunction "NC.3_3") (pintype "bidirectional"))
    )
    (net (code "78") (name "unconnected-(U1-S-NC.4-Pad4)") (class "Default")
      (node (ref "U1-S") (pin "4") (pinfunction "NC.4_4") (pintype "bidirectional"))
    )
    (net (code "79") (name "unconnected-(U1-S-NC.5-Pad5)") (class "Default")
      (node (ref "U1-S") (pin "5") (pinfunction "NC.5_5") (pintype "bidirectional"))
    )
    (net (code "80") (name "unconnected-(U1-S-NC.6-Pad6)") (class "Default")
      (node (ref "U1-S") (pin "6") (pinfunction "NC.6_6") (pintype "bidirectional"))
    )
    (net (code "81") (name "unconnected-(U1-S-NC.14-Pad14)") (class "Default")
      (node (ref "U1-S") (pin "14") (pinfunction "NC.14_14") (pintype "bidirectional"))
    )
    (net (code "82") (name "unconnected-(U1-S-NC.15-Pad15)") (class "Default")
      (node (ref "U1-S") (pin "15") (pinfunction "NC.15_15") (pintype "bidirectional"))
    )
    (net (code "83") (name "unconnected-(U1-S-NC.16-Pad16)") (class "Default")
      (node (ref "U1-S") (pin "16") (pinfunction "NC.16_16") (pintype "bidirectional"))
    )
    (net (code "84") (name "unconnected-(U1-S-NC.17-Pad17)") (class "Default")
      (node (ref "U1-S") (pin "17") (pinfunction "NC.17_17") (pintype "bidirectional"))
    )
    (net (code "85") (name "unconnected-(U1-S-RESV.NC-Pad19)") (class "Default")
      (node (ref "U1-S") (pin "19") (pinfunction "RESV.NC_19") (pintype "bidirectional"))
    )
  )
)
